# Cap_Array_100p_400n.net
KiCad netlist of a schematic drawn in Altium Designer
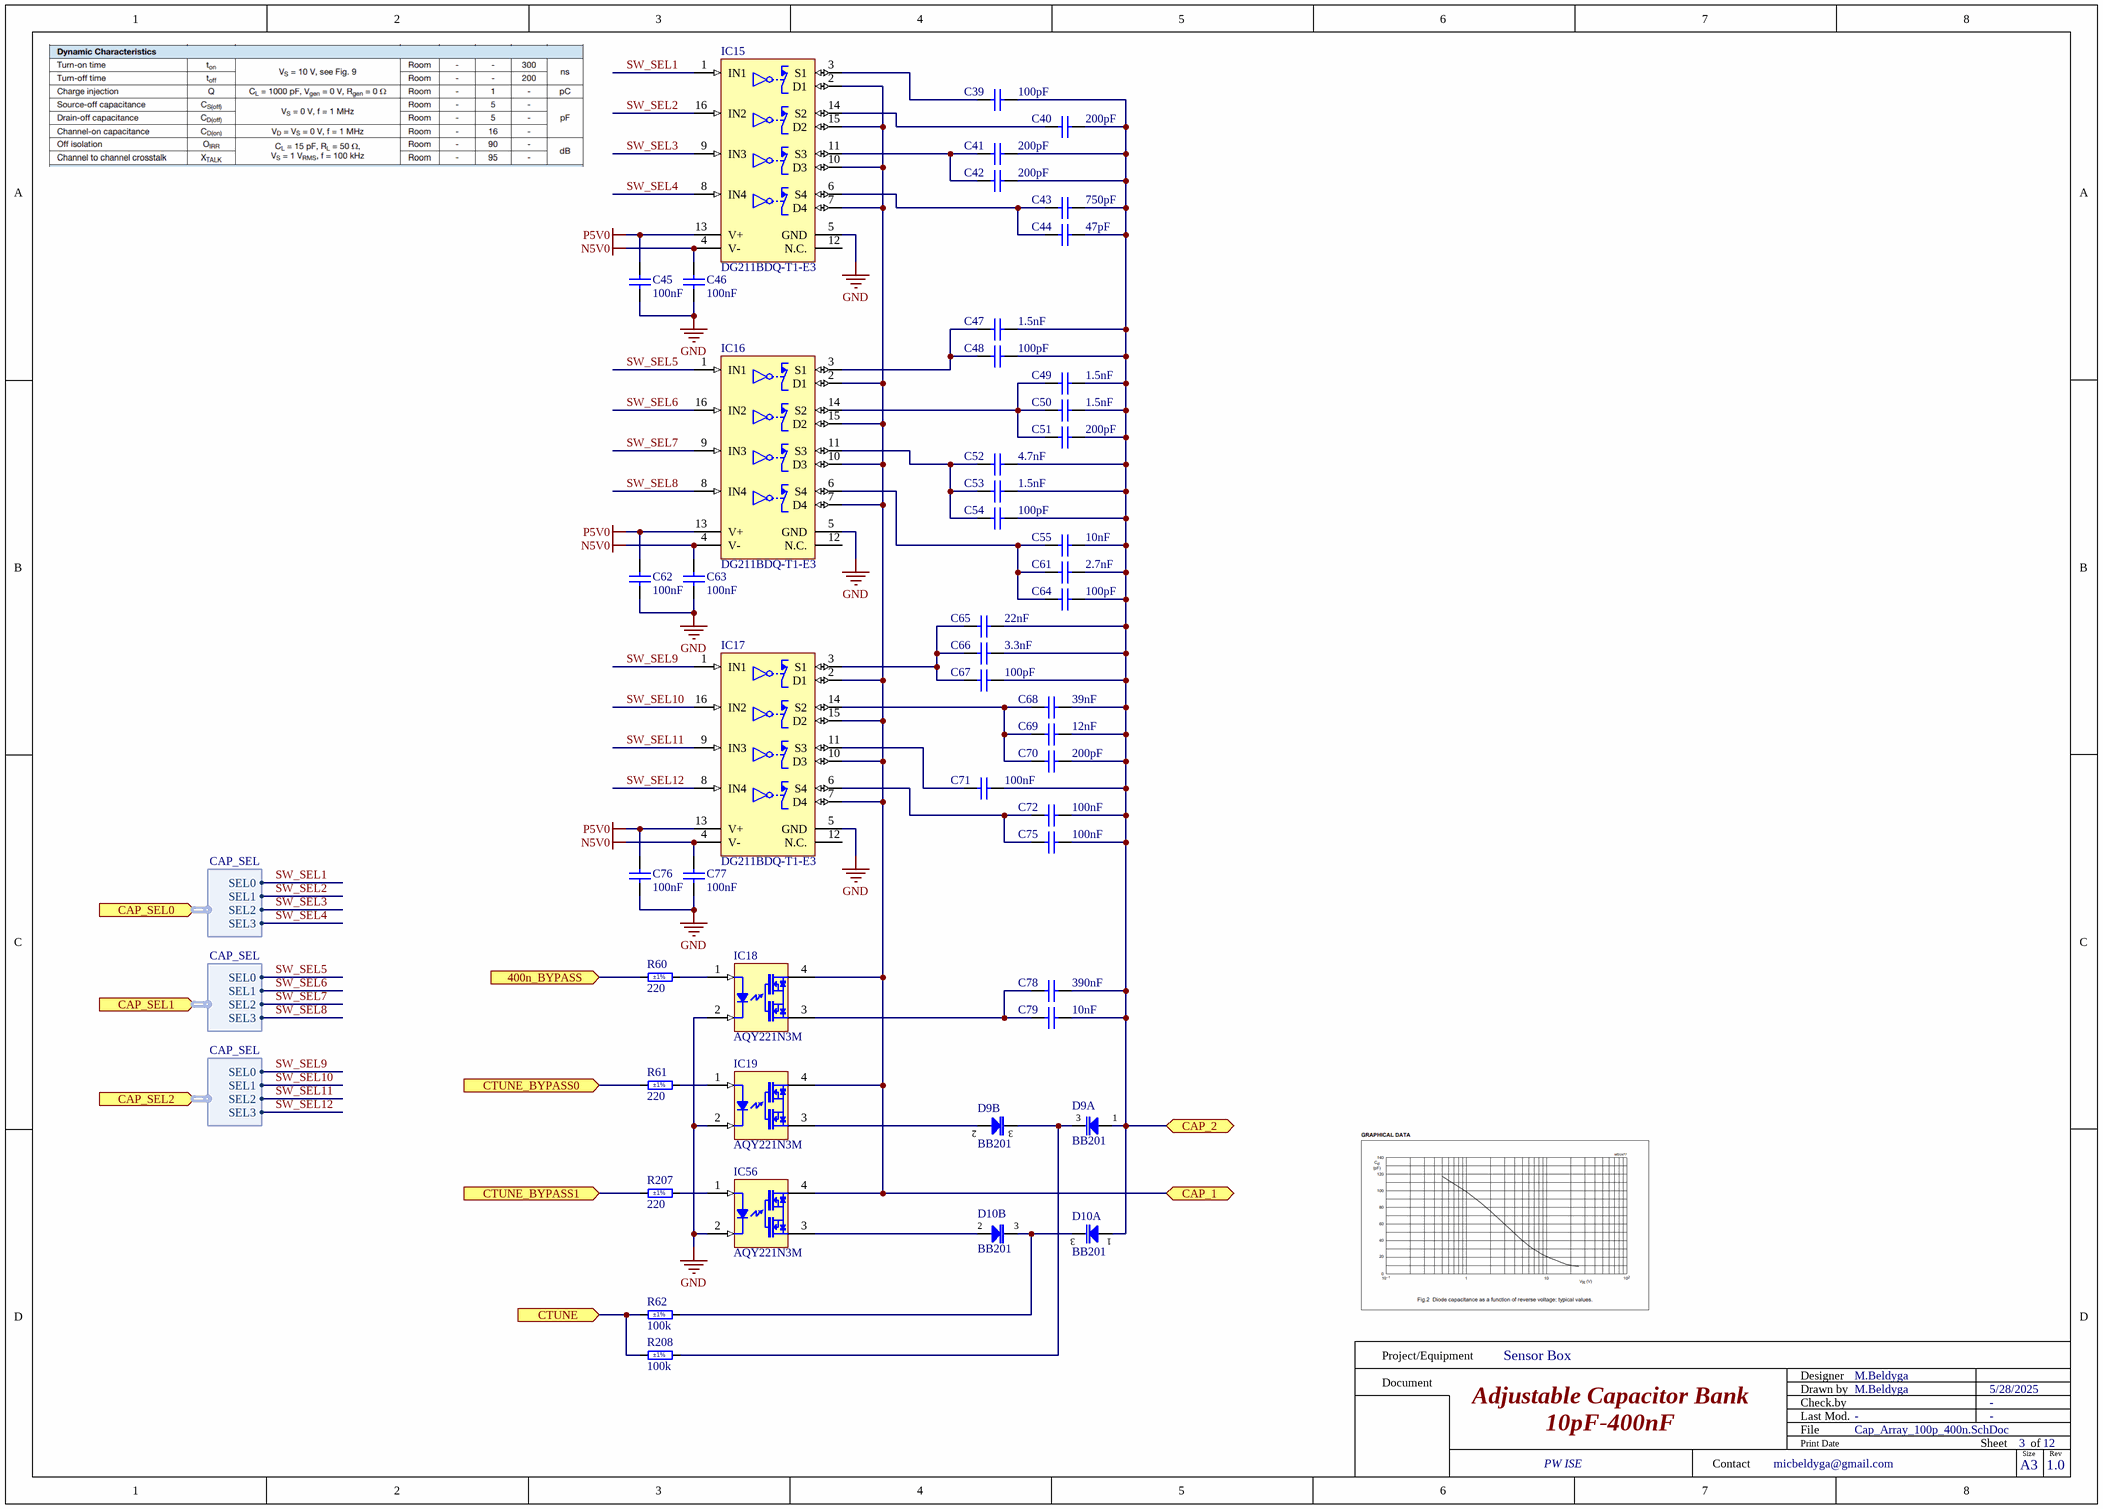
[diagram p0: Cap_Array_100p_400n.SchDoc]

(export (version "E")
  (design (tool "Eeschema 10.0.6"))
  (components
    (comp (ref "C39")
      (value "100pF")
      (footprint "CAPC1005X55N")
      (description "Non-polarised capacitor")
      (fields
        (field (name "PART NUMBER") "CC0402_100PF_25V_1%_C0G")
        (field (name "VOLTAGE") "25V")
        (field (name "AUTHOR") "CERN DEM HF")
      )
      (libsource (lib "Capacitors") (part "Capacitor - non polarized"))
    )
    (comp (ref "C40")
      (value "200pF")
      (footprint "CAPC1005X55N")
      (description "Multilayer Ceramic Capacitor, 200 pF, 50 V, ï¿½ 1%, C0G (NP0), 0402 [1005 Metric]")
      (fields
        (field (name "MANUFACTURER") "Murata")
        (field (name "MANUFACTURER PART NUMBER") "GCM1555C1H201FA16D")
      )
      (libsource (lib "mb") (part "0402 200pF 50V"))
    )
    (comp (ref "C41")
      (value "200pF")
      (footprint "CAPC1005X55N")
      (description "Multilayer Ceramic Capacitor, 200 pF, 50 V, ï¿½ 1%, C0G (NP0), 0402 [1005 Metric]")
      (fields
        (field (name "MANUFACTURER") "Murata")
        (field (name "MANUFACTURER PART NUMBER") "GCM1555C1H201FA16D")
      )
      (libsource (lib "mb") (part "0402 200pF 50V"))
    )
    (comp (ref "C42")
      (value "200pF")
      (footprint "CAPC1005X55N")
      (description "Multilayer Ceramic Capacitor, 200 pF, 50 V, ï¿½ 1%, C0G (NP0), 0402 [1005 Metric]")
      (fields
        (field (name "MANUFACTURER") "Murata")
        (field (name "MANUFACTURER PART NUMBER") "GCM1555C1H201FA16D")
      )
      (libsource (lib "mb") (part "0402 200pF 50V"))
    )
    (comp (ref "C43")
      (value "750pF")
      (footprint "CAPC1005X55N")
      (description "Cap Auto-grade 750PF 50VDC C0G 1% SMD 0402")
      (fields
        (field (name "MANUFACTURER") "Murata")
        (field (name "MANUFACTURER PART NUMBER") "GCM1555C1H751FA16D")
      )
      (libsource (lib "mb") (part "0402 750pF 50V"))
    )
    (comp (ref "C44")
      (value "47pF")
      (footprint "CAPC1005X55N")
      (description "Non-polarised capacitor")
      (fields
        (field (name "PART NUMBER") "CC0402_47PF_50V_1%_C0G_MURATA_GJM1555C1H470FB01D")
        (field (name "VOLTAGE") "50V")
        (field (name "AUTHOR") "CERN DEM BC")
      )
      (libsource (lib "Capacitors") (part "Capacitor - non polarized"))
    )
    (comp (ref "C45")
      (value "100nF")
      (footprint "CAPC1005X55N")
      (description "Non-polarised capacitor")
      (fields
        (field (name "PART NUMBER") "CC0402_100NF_50V_10%_X7R")
        (field (name "VOLTAGE") "50V")
        (field (name "AUTHOR") "CERN DEM MR")
      )
      (libsource (lib "Capacitors") (part "Capacitor - non polarized"))
    )
    (comp (ref "C46")
      (value "100nF")
      (footprint "CAPC1005X55N")
      (description "Non-polarised capacitor")
      (fields
        (field (name "PART NUMBER") "CC0402_100NF_50V_10%_X7R")
        (field (name "VOLTAGE") "50V")
        (field (name "AUTHOR") "CERN DEM MR")
      )
      (libsource (lib "Capacitors") (part "Capacitor - non polarized"))
    )
    (comp (ref "C47")
      (value "1.5nF")
      (footprint "CAPC1005X55N")
      (fields
        (field (name "MANUFACTURER") "KEMET")
        (field (name "MANUFACTURER PART NUMBER") "C0402C152F5GECAUTO")
      )
      (libsource (lib "mb") (part "0402 1.5nF 50V"))
    )
    (comp (ref "C48")
      (value "100pF")
      (footprint "CAPC1005X55N")
      (description "Non-polarised capacitor")
      (fields
        (field (name "PART NUMBER") "CC0402_100PF_25V_1%_C0G")
        (field (name "VOLTAGE") "25V")
        (field (name "AUTHOR") "CERN DEM HF")
      )
      (libsource (lib "Capacitors") (part "Capacitor - non polarized"))
    )
    (comp (ref "C49")
      (value "1.5nF")
      (footprint "CAPC1005X55N")
      (fields
        (field (name "MANUFACTURER") "KEMET")
        (field (name "MANUFACTURER PART NUMBER") "C0402C152F5GECAUTO")
      )
      (libsource (lib "mb") (part "0402 1.5nF 50V"))
    )
    (comp (ref "C50")
      (value "1.5nF")
      (footprint "CAPC1005X55N")
      (fields
        (field (name "MANUFACTURER") "KEMET")
        (field (name "MANUFACTURER PART NUMBER") "C0402C152F5GECAUTO")
      )
      (libsource (lib "mb") (part "0402 1.5nF 50V"))
    )
    (comp (ref "C51")
      (value "200pF")
      (footprint "CAPC1005X55N")
      (description "Multilayer Ceramic Capacitor, 200 pF, 50 V, ï¿½ 1%, C0G (NP0), 0402 [1005 Metric]")
      (fields
        (field (name "MANUFACTURER") "Murata")
        (field (name "MANUFACTURER PART NUMBER") "GCM1555C1H201FA16D")
      )
      (libsource (lib "mb") (part "0402 200pF 50V"))
    )
    (comp (ref "C52")
      (value "4.7nF")
      (footprint "CAPC1608X90N")
      (description "Cap Ceramic 0.0047uF 50V C0G 1% Pad SMD 0603 125°C Automotive T/R")
      (fields
        (field (name "MANUFACTURER") "Murata")
        (field (name "MANUFACTURER PART NUMBER") "GCM1885C1H472FA16D")
      )
      (libsource (lib "mb") (part "0603 4.7nF 50V"))
    )
    (comp (ref "C53")
      (value "1.5nF")
      (footprint "CAPC1005X55N")
      (fields
        (field (name "MANUFACTURER") "KEMET")
        (field (name "MANUFACTURER PART NUMBER") "C0402C152F5GECAUTO")
      )
      (libsource (lib "mb") (part "0402 1.5nF 50V"))
    )
    (comp (ref "C54")
      (value "100pF")
      (footprint "CAPC1005X55N")
      (description "Non-polarised capacitor")
      (fields
        (field (name "PART NUMBER") "CC0402_100PF_25V_1%_C0G")
        (field (name "VOLTAGE") "25V")
        (field (name "AUTHOR") "CERN DEM HF")
      )
      (libsource (lib "Capacitors") (part "Capacitor - non polarized"))
    )
    (comp (ref "C55")
      (value "10nF")
      (footprint "CAPC1608X90N")
      (description "Multilayer Ceramic Capacitors MLCC - SMD/SMT 25V 0.01uF C0G 0603 1% AEC-Q200")
      (fields
        (field (name "MANUFACTURER") "KEMET")
        (field (name "MANUFACTURER PART NUMBER") "C0603C103F3GECAUTO")
      )
      (libsource (lib "mb") (part "0603 10nF 25V"))
    )
    (comp (ref "C61")
      (value "2.7nF")
      (footprint "CAPC1608X90N")
      (description "Powerrain/Safety for Automotive AEC-Q200 Up to 125C Reflow soldering Flow soldering")
      (fields
        (field (name "MANUFACTURER") "Murata")
        (field (name "MANUFACTURER PART NUMBER") "GCM1885C1H272FA16J")
      )
      (libsource (lib "mb") (part "0603 2.7nF 50V"))
    )
    (comp (ref "C62")
      (value "100nF")
      (footprint "CAPC1005X55N")
      (description "Non-polarised capacitor")
      (fields
        (field (name "PART NUMBER") "CC0402_100NF_50V_10%_X7R")
        (field (name "VOLTAGE") "50V")
        (field (name "AUTHOR") "CERN DEM MR")
      )
      (libsource (lib "Capacitors") (part "Capacitor - non polarized"))
    )
    (comp (ref "C63")
      (value "100nF")
      (footprint "CAPC1005X55N")
      (description "Non-polarised capacitor")
      (fields
        (field (name "PART NUMBER") "CC0402_100NF_50V_10%_X7R")
        (field (name "VOLTAGE") "50V")
        (field (name "AUTHOR") "CERN DEM MR")
      )
      (libsource (lib "Capacitors") (part "Capacitor - non polarized"))
    )
    (comp (ref "C64")
      (value "100pF")
      (footprint "CAPC1005X55N")
      (description "Non-polarised capacitor")
      (fields
        (field (name "PART NUMBER") "CC0402_100PF_25V_1%_C0G")
        (field (name "VOLTAGE") "25V")
        (field (name "AUTHOR") "CERN DEM HF")
      )
      (libsource (lib "Capacitors") (part "Capacitor - non polarized"))
    )
    (comp (ref "C65")
      (value "22nF")
      (footprint "CAPC2012X95N")
      (description "0805 50V C0G 0.022uF 1% Automotive grade multilayer ceramic capacitor")
      (fields
        (field (name "MANUFACTURER") "Murata")
        (field (name "MANUFACTURER PART NUMBER") "GCM21B5C1H223FA16L")
      )
      (libsource (lib "mb") (part "0805 22nF 50V"))
    )
    (comp (ref "C66")
      (value "3.3nF")
      (footprint "CAPC1608X90N")
      (description "Cap Ceramic 0.0033uF 50V C0G 1% Pad SMD 0603 125°C Automotive T/R")
      (fields
        (field (name "MANUFACTURER") "Murata")
        (field (name "MANUFACTURER PART NUMBER") "GCM1885C1H332FA16D")
      )
      (libsource (lib "mb") (part "0603 3.3nF 50V"))
    )
    (comp (ref "C67")
      (value "100pF")
      (footprint "CAPC1005X55N")
      (description "Non-polarised capacitor")
      (fields
        (field (name "PART NUMBER") "CC0402_100PF_25V_1%_C0G")
        (field (name "VOLTAGE") "25V")
        (field (name "AUTHOR") "CERN DEM HF")
      )
      (libsource (lib "Capacitors") (part "Capacitor - non polarized"))
    )
    (comp (ref "C68")
      (value "39nF")
      (footprint "CAPC2012X95N")
      (description "Multilayer Ceramic Capacitors MLCC - SMD/SMT 0805 C0G 39000pF 2% 100VDC")
      (fields
        (field (name "MANUFACTURER") "Murata")
        (field (name "MANUFACTURER PART NUMBER") "GRM2195C2A393GE01J")
      )
      (libsource (lib "mb") (part "0805 39nF 100V"))
    )
    (comp (ref "C69")
      (value "12nF")
      (footprint "CAPC1608X90N")
      (description "Cap Ceramic 0.012uF 25V C0G 1% Pad SMD 0603 125°C Extreme Low ESR T/R")
      (fields
        (field (name "MANUFACTURER") "KEMET")
        (field (name "MANUFACTURER PART NUMBER") "C0603C123F3GACTU")
      )
      (libsource (lib "mb") (part "0603 12nF 25V"))
    )
    (comp (ref "C70")
      (value "200pF")
      (footprint "CAPC1005X55N")
      (description "Multilayer Ceramic Capacitor, 200 pF, 50 V, ï¿½ 1%, C0G (NP0), 0402 [1005 Metric]")
      (fields
        (field (name "MANUFACTURER") "Murata")
        (field (name "MANUFACTURER PART NUMBER") "GCM1555C1H201FA16D")
      )
      (libsource (lib "mb") (part "0402 200pF 50V"))
    )
    (comp (ref "C71")
      (value "100nF")
      (footprint "CAPC1810X06N")
      (description "Cap Cer 0.1UF 50V C0G/NP0 0704")
      (fields
        (field (name "MANUFACTURER") "Murata")
        (field (name "MANUFACTURER PART NUMBER") "GRMJN65C1H104GE01J")
      )
      (libsource (lib "mb") (part "0704 100nF 50V"))
    )
    (comp (ref "C72")
      (value "100nF")
      (footprint "CAPC1810X06N")
      (description "Cap Cer 0.1UF 50V C0G/NP0 0704")
      (fields
        (field (name "MANUFACTURER") "Murata")
        (field (name "MANUFACTURER PART NUMBER") "GRMJN65C1H104GE01J")
      )
      (libsource (lib "mb") (part "0704 100nF 50V"))
    )
    (comp (ref "C75")
      (value "100nF")
      (footprint "CAPC1810X06N")
      (description "Cap Cer 0.1UF 50V C0G/NP0 0704")
      (fields
        (field (name "MANUFACTURER") "Murata")
        (field (name "MANUFACTURER PART NUMBER") "GRMJN65C1H104GE01J")
      )
      (libsource (lib "mb") (part "0704 100nF 50V"))
    )
    (comp (ref "C76")
      (value "100nF")
      (footprint "CAPC1005X55N")
      (description "Non-polarised capacitor")
      (fields
        (field (name "PART NUMBER") "CC0402_100NF_50V_10%_X7R")
        (field (name "VOLTAGE") "50V")
        (field (name "AUTHOR") "CERN DEM MR")
      )
      (libsource (lib "Capacitors") (part "Capacitor - non polarized"))
    )
    (comp (ref "C77")
      (value "100nF")
      (footprint "CAPC1005X55N")
      (description "Non-polarised capacitor")
      (fields
        (field (name "PART NUMBER") "CC0402_100NF_50V_10%_X7R")
        (field (name "VOLTAGE") "50V")
        (field (name "AUTHOR") "CERN DEM MR")
      )
      (libsource (lib "Capacitors") (part "Capacitor - non polarized"))
    )
    (comp (ref "C78")
      (value "390nF")
      (footprint "CAPC1608X90N")
      (description "Cap Ceramic 0.39uF 16V X7R 5% Pad SMD 0603 125C T/R")
      (fields
        (field (name "MANUFACTURER") "KEMET")
        (field (name "MANUFACTURER PART NUMBER") "C0603C394J4RACTU")
      )
      (libsource (lib "mb") (part "0603 390nF 16V"))
    )
    (comp (ref "C79")
      (value "10nF")
      (footprint "CAPC1608X90N")
      (description "Multilayer Ceramic Capacitors MLCC - SMD/SMT 25V 0.01uF C0G 0603 1% AEC-Q200")
      (fields
        (field (name "MANUFACTURER") "KEMET")
        (field (name "MANUFACTURER PART NUMBER") "C0603C103F3GECAUTO")
      )
      (libsource (lib "mb") (part "0603 10nF 25V"))
    )
    (comp (ref "D9")
      (value "BB201")
      (footprint "SOT95P230X110-3N")
      (description "Dual Common Cathode Varicap Diodes")
      (fields
        (field (name "VOLTAGE") "15V")
        (field (name "POWER") "20mA")
        (field (name "AUTHOR") "CERN DEM JLC")
      )
      (libsource (lib "ICs And Semiconductors") (part "Diode Varicap x2 A1C3_A2C3"))
    )
    (comp (ref "D10")
      (value "BB201")
      (footprint "SOT95P230X110-3N")
      (description "Dual Common Cathode Varicap Diodes")
      (fields
        (field (name "VOLTAGE") "15V")
        (field (name "POWER") "20mA")
        (field (name "AUTHOR") "CERN DEM JLC")
      )
      (libsource (lib "") (part "Diode Varicap x2 A1C3_A2C3_1"))
    )
    (comp (ref "IC15")
      (value "DG211BDQ-T1-E3")
      (footprint "SOP65P640X120-16N")
      (description "DG211B Series SPST 22 V 50 Ohm Surface Mount Improved Analog Switch - TSSOP-16")
      (fields (field (name "MANUFACTURER") "Vishay Siliconix"))
      (libsource (lib "mb") (part "DG211BDQ-T1-E3"))
    )
    (comp (ref "IC16")
      (value "DG211BDQ-T1-E3")
      (footprint "SOP65P640X120-16N")
      (description "DG211B Series SPST 22 V 50 Ohm Surface Mount Improved Analog Switch - TSSOP-16")
      (fields (field (name "MANUFACTURER") "Vishay Siliconix"))
      (libsource (lib "mb") (part "DG211BDQ-T1-E3"))
    )
    (comp (ref "IC17")
      (value "DG211BDQ-T1-E3")
      (footprint "SOP65P640X120-16N")
      (description "DG211B Series SPST 22 V 50 Ohm Surface Mount Improved Analog Switch - TSSOP-16")
      (fields (field (name "MANUFACTURER") "Vishay Siliconix"))
      (libsource (lib "mb") (part "DG211BDQ-T1-E3"))
    )
    (comp (ref "IC18")
      (value "AQY221N3M")
      (footprint "PANASONIC_AQY22(SON)")
      (description "PhotoMOS Relay")
      (fields (field (name "MANUFACTURER") "PANASONIC") (field (name "AUTHOR") "CERN DEM JLC"))
      (libsource (lib "ICs And Semiconductors") (part "PhotoMOS Relay x1 Type5_a"))
    )
    (comp (ref "IC19")
      (value "AQY221N3M")
      (footprint "PANASONIC_AQY22(SON)")
      (description "PhotoMOS Relay")
      (fields (field (name "MANUFACTURER") "PANASONIC") (field (name "AUTHOR") "CERN DEM JLC"))
      (libsource (lib "ICs And Semiconductors") (part "PhotoMOS Relay x1 Type5_a"))
    )
    (comp (ref "IC56")
      (value "AQY221N3M")
      (footprint "PANASONIC_AQY22(SON)")
      (description "PhotoMOS Relay")
      (fields (field (name "MANUFACTURER") "PANASONIC") (field (name "AUTHOR") "CERN DEM JLC"))
      (libsource (lib "ICs And Semiconductors") (part "PhotoMOS Relay x1 Type5_a"))
    )
    (comp (ref "R60")
      (value "220")
      (footprint "RESC1005X40N")
      (description "Resistor - 1%")
      (fields
        (field (name "TOLERANCE") "±1%")
        (field (name "PART NUMBER") "R0402_220R_1%_0.0625W_100PPM")
        (field (name "POWER") "0.0625W")
        (field (name "AUTHOR") "CERN DEM JLC")
      )
      (libsource (lib "Resistors") (part "Resistor - 1%"))
    )
    (comp (ref "R61")
      (value "220")
      (footprint "RESC1005X40N")
      (description "Resistor - 1%")
      (fields
        (field (name "TOLERANCE") "±1%")
        (field (name "PART NUMBER") "R0402_220R_1%_0.0625W_100PPM")
        (field (name "POWER") "0.0625W")
        (field (name "AUTHOR") "CERN DEM JLC")
      )
      (libsource (lib "Resistors") (part "Resistor - 1%"))
    )
    (comp (ref "R62")
      (value "100k")
      (footprint "RESC1005X40N")
      (description "Resistor - 1%")
      (fields
        (field (name "TOLERANCE") "±1%")
        (field (name "PART NUMBER") "R0402_100K_1%_0.0625W_100PPM")
        (field (name "POWER") "0.0625W")
        (field (name "AUTHOR") "CERN DEM JLC")
      )
      (libsource (lib "Resistors") (part "Resistor - 1%"))
    )
    (comp (ref "R207")
      (value "220")
      (footprint "RESC1005X40N")
      (description "Resistor - 1%")
      (fields
        (field (name "TOLERANCE") "±1%")
        (field (name "PART NUMBER") "R0402_220R_1%_0.0625W_100PPM")
        (field (name "POWER") "0.0625W")
        (field (name "AUTHOR") "CERN DEM JLC")
      )
      (libsource (lib "Resistors") (part "Resistor - 1%"))
    )
    (comp (ref "R208")
      (value "100k")
      (footprint "RESC1005X40N")
      (description "Resistor - 1%")
      (fields
        (field (name "TOLERANCE") "±1%")
        (field (name "PART NUMBER") "R0402_100K_1%_0.0625W_100PPM")
        (field (name "POWER") "0.0625W")
        (field (name "AUTHOR") "CERN DEM JLC")
      )
      (libsource (lib "Resistors") (part "Resistor - 1%"))
    )
  )
  (nets
    (net (code "2") (name "/400n_BYPASS") (class "Default")
      (node (ref "R60") (pin "1") (pinfunction "1_1") (pintype "passive"))
    )
    (net (code "3") (name "/CAP_1") (class "Default")
      (node (ref "IC15") (pin "10") (pinfunction "D3_10") (pintype "bidirectional"))
      (node (ref "IC15") (pin "15") (pinfunction "D2_15") (pintype "bidirectional"))
      (node (ref "IC15") (pin "2") (pinfunction "D1_2") (pintype "bidirectional"))
      (node (ref "IC15") (pin "7") (pinfunction "D4_7") (pintype "bidirectional"))
      (node (ref "IC16") (pin "10") (pinfunction "D3_10") (pintype "bidirectional"))
      (node (ref "IC16") (pin "15") (pinfunction "D2_15") (pintype "bidirectional"))
      (node (ref "IC16") (pin "2") (pinfunction "D1_2") (pintype "bidirectional"))
      (node (ref "IC16") (pin "7") (pinfunction "D4_7") (pintype "bidirectional"))
      (node (ref "IC17") (pin "10") (pinfunction "D3_10") (pintype "bidirectional"))
      (node (ref "IC17") (pin "15") (pinfunction "D2_15") (pintype "bidirectional"))
      (node (ref "IC17") (pin "2") (pinfunction "D1_2") (pintype "bidirectional"))
      (node (ref "IC17") (pin "7") (pinfunction "D4_7") (pintype "bidirectional"))
      (node (ref "IC18") (pin "4") (pinfunction "E_4") (pintype "open_emitter"))
      (node (ref "IC19") (pin "4") (pinfunction "E_4") (pintype "open_emitter"))
      (node (ref "IC56") (pin "4") (pinfunction "E_4") (pintype "open_emitter"))
    )
    (net (code "4") (name "/CAP_2") (class "Default")
      (node (ref "C39") (pin "2") (pinfunction "2_2") (pintype "passive"))
      (node (ref "C40") (pin "1") (pinfunction "1_1") (pintype "passive"))
      (node (ref "C41") (pin "1") (pinfunction "1_1") (pintype "passive"))
      (node (ref "C42") (pin "1") (pinfunction "1_1") (pintype "passive"))
      (node (ref "C43") (pin "1") (pinfunction "1_1") (pintype "passive"))
      (node (ref "C44") (pin "2") (pinfunction "2_2") (pintype "passive"))
      (node (ref "C47") (pin "1") (pinfunction "1_1") (pintype "passive"))
      (node (ref "C48") (pin "2") (pinfunction "2_2") (pintype "passive"))
      (node (ref "C49") (pin "1") (pinfunction "1_1") (pintype "passive"))
      (node (ref "C50") (pin "1") (pinfunction "1_1") (pintype "passive"))
      (node (ref "C51") (pin "1") (pinfunction "1_1") (pintype "passive"))
      (node (ref "C52") (pin "1") (pinfunction "1_1") (pintype "passive"))
      (node (ref "C53") (pin "1") (pinfunction "1_1") (pintype "passive"))
      (node (ref "C54") (pin "2") (pinfunction "2_2") (pintype "passive"))
      (node (ref "C55") (pin "1") (pinfunction "1_1") (pintype "passive"))
      (node (ref "C61") (pin "1") (pinfunction "1_1") (pintype "passive"))
      (node (ref "C64") (pin "2") (pinfunction "2_2") (pintype "passive"))
      (node (ref "C65") (pin "1") (pinfunction "1_1") (pintype "passive"))
      (node (ref "C66") (pin "1") (pinfunction "1_1") (pintype "passive"))
      (node (ref "C67") (pin "2") (pinfunction "2_2") (pintype "passive"))
      (node (ref "C68") (pin "1") (pinfunction "1_1") (pintype "passive"))
      (node (ref "C69") (pin "1") (pinfunction "1_1") (pintype "passive"))
      (node (ref "C70") (pin "1") (pinfunction "1_1") (pintype "passive"))
      (node (ref "C71") (pin "1") (pinfunction "1_1") (pintype "passive"))
      (node (ref "C72") (pin "1") (pinfunction "1_1") (pintype "passive"))
      (node (ref "C75") (pin "1") (pinfunction "1_1") (pintype "passive"))
      (node (ref "C78") (pin "1") (pinfunction "1_1") (pintype "passive"))
      (node (ref "C79") (pin "1") (pinfunction "1_1") (pintype "passive"))
      (node (ref "D10") (pin "1") (pinfunction "A_1") (pintype "passive"))
      (node (ref "D9") (pin "1") (pinfunction "A_1") (pintype "passive"))
    )
    (net (code "5") (name "/CTUNE") (class "Default")
      (node (ref "R208") (pin "2") (pinfunction "2_2") (pintype "passive"))
      (node (ref "R62") (pin "2") (pinfunction "2_2") (pintype "passive"))
    )
    (net (code "6") (name "/CTUNE_BYPASS0") (class "Default")
      (node (ref "R61") (pin "1") (pinfunction "1_1") (pintype "passive"))
    )
    (net (code "7") (name "/CTUNE_BYPASS1") (class "Default")
      (node (ref "R207") (pin "1") (pinfunction "1_1") (pintype "passive"))
    )
    (net (code "8") (name "/SW_SEL1") (class "Default")
      (node (ref "IC15") (pin "1") (pinfunction "IN1_1") (pintype "input"))
    )
    (net (code "9") (name "/SW_SEL2") (class "Default")
      (node (ref "IC15") (pin "16") (pinfunction "IN2_16") (pintype "input"))
    )
    (net (code "10") (name "/SW_SEL3") (class "Default")
      (node (ref "IC15") (pin "9") (pinfunction "IN3_9") (pintype "input"))
    )
    (net (code "11") (name "/SW_SEL4") (class "Default")
      (node (ref "IC15") (pin "8") (pinfunction "IN4_8") (pintype "input"))
    )
    (net (code "12") (name "/SW_SEL5") (class "Default")
      (node (ref "IC16") (pin "1") (pinfunction "IN1_1") (pintype "input"))
    )
    (net (code "13") (name "/SW_SEL6") (class "Default")
      (node (ref "IC16") (pin "16") (pinfunction "IN2_16") (pintype "input"))
    )
    (net (code "14") (name "/SW_SEL7") (class "Default")
      (node (ref "IC16") (pin "9") (pinfunction "IN3_9") (pintype "input"))
    )
    (net (code "15") (name "/SW_SEL8") (class "Default")
      (node (ref "IC16") (pin "8") (pinfunction "IN4_8") (pintype "input"))
    )
    (net (code "16") (name "/SW_SEL9") (class "Default")
      (node (ref "IC17") (pin "1") (pinfunction "IN1_1") (pintype "input"))
    )
    (net (code "17") (name "/SW_SEL10") (class "Default")
      (node (ref "IC17") (pin "16") (pinfunction "IN2_16") (pintype "input"))
    )
    (net (code "18") (name "/SW_SEL11") (class "Default")
      (node (ref "IC17") (pin "9") (pinfunction "IN3_9") (pintype "input"))
    )
    (net (code "19") (name "/SW_SEL12") (class "Default")
      (node (ref "IC17") (pin "8") (pinfunction "IN4_8") (pintype "input"))
    )
    (net (code "21") (name "GND") (class "Default")
      (node (ref "C45") (pin "1") (pinfunction "1_1") (pintype "passive"))
      (node (ref "C46") (pin "1") (pinfunction "1_1") (pintype "passive"))
      (node (ref "C62") (pin "1") (pinfunction "1_1") (pintype "passive"))
      (node (ref "C63") (pin "1") (pinfunction "1_1") (pintype "passive"))
      (node (ref "C76") (pin "1") (pinfunction "1_1") (pintype "passive"))
      (node (ref "C77") (pin "1") (pinfunction "1_1") (pintype "passive"))
      (node (ref "IC15") (pin "5") (pinfunction "GND_5") (pintype "power_in"))
      (node (ref "IC16") (pin "5") (pinfunction "GND_5") (pintype "power_in"))
      (node (ref "IC17") (pin "5") (pinfunction "GND_5") (pintype "power_in"))
      (node (ref "IC18") (pin "2") (pinfunction "K_2") (pintype "input"))
      (node (ref "IC19") (pin "2") (pinfunction "K_2") (pintype "input"))
      (node (ref "IC56") (pin "2") (pinfunction "K_2") (pintype "input"))
    )
    (net (code "22") (name "N5V0") (class "Default")
      (node (ref "C46") (pin "2") (pinfunction "2_2") (pintype "passive"))
      (node (ref "C63") (pin "2") (pinfunction "2_2") (pintype "passive"))
      (node (ref "C77") (pin "2") (pinfunction "2_2") (pintype "passive"))
      (node (ref "IC15") (pin "4") (pinfunction "V-_4") (pintype "power_in"))
      (node (ref "IC16") (pin "4") (pinfunction "V-_4") (pintype "power_in"))
      (node (ref "IC17") (pin "4") (pinfunction "V-_4") (pintype "power_in"))
    )
    (net (code "23") (name "Net-(D9A-COMC)") (class "Default")
      (node (ref "D9") (pin "3") (pinfunction "COMC_3") (pintype "passive"))
      (node (ref "R208") (pin "1") (pinfunction "1_1") (pintype "passive"))
    )
    (net (code "24") (name "Net-(D9B-A)") (class "Default")
      (node (ref "D9") (pin "2") (pinfunction "A_2") (pintype "passive"))
      (node (ref "IC19") (pin "3") (pinfunction "C_3") (pintype "open_collector"))
    )
    (net (code "25") (name "Net-(D10A-COMC)") (class "Default")
      (node (ref "D10") (pin "3") (pinfunction "COMC_3") (pintype "passive"))
      (node (ref "R62") (pin "1") (pinfunction "1_1") (pintype "passive"))
    )
    (net (code "26") (name "Net-(D10B-A)") (class "Default")
      (node (ref "D10") (pin "2") (pinfunction "A_2") (pintype "passive"))
      (node (ref "IC56") (pin "3") (pinfunction "C_3") (pintype "open_collector"))
    )
    (net (code "27") (name "Net-(IC15-S1)") (class "Default")
      (node (ref "C39") (pin "1") (pinfunction "1_1") (pintype "passive"))
      (node (ref "IC15") (pin "3") (pinfunction "S1_3") (pintype "bidirectional"))
    )
    (net (code "28") (name "Net-(IC15-S2)") (class "Default")
      (node (ref "C40") (pin "2") (pinfunction "2_2") (pintype "passive"))
      (node (ref "IC15") (pin "14") (pinfunction "S2_14") (pintype "bidirectional"))
    )
    (net (code "29") (name "Net-(IC15-S3)") (class "Default")
      (node (ref "C41") (pin "2") (pinfunction "2_2") (pintype "passive"))
      (node (ref "C42") (pin "2") (pinfunction "2_2") (pintype "passive"))
      (node (ref "IC15") (pin "11") (pinfunction "S3_11") (pintype "bidirectional"))
    )
    (net (code "30") (name "Net-(IC15-S4)") (class "Default")
      (node (ref "C43") (pin "2") (pinfunction "2_2") (pintype "passive"))
      (node (ref "C44") (pin "1") (pinfunction "1_1") (pintype "passive"))
      (node (ref "IC15") (pin "6") (pinfunction "S4_6") (pintype "bidirectional"))
    )
    (net (code "31") (name "Net-(IC16-S1)") (class "Default")
      (node (ref "C47") (pin "2") (pinfunction "2_2") (pintype "passive"))
      (node (ref "C48") (pin "1") (pinfunction "1_1") (pintype "passive"))
      (node (ref "IC16") (pin "3") (pinfunction "S1_3") (pintype "bidirectional"))
    )
    (net (code "32") (name "Net-(IC16-S2)") (class "Default")
      (node (ref "C49") (pin "2") (pinfunction "2_2") (pintype "passive"))
      (node (ref "C50") (pin "2") (pinfunction "2_2") (pintype "passive"))
      (node (ref "C51") (pin "2") (pinfunction "2_2") (pintype "passive"))
      (node (ref "IC16") (pin "14") (pinfunction "S2_14") (pintype "bidirectional"))
    )
    (net (code "33") (name "Net-(IC16-S3)") (class "Default")
      (node (ref "C52") (pin "2") (pinfunction "2_2") (pintype "passive"))
      (node (ref "C53") (pin "2") (pinfunction "2_2") (pintype "passive"))
      (node (ref "C54") (pin "1") (pinfunction "1_1") (pintype "passive"))
      (node (ref "IC16") (pin "11") (pinfunction "S3_11") (pintype "bidirectional"))
    )
    (net (code "34") (name "Net-(IC16-S4)") (class "Default")
      (node (ref "C55") (pin "2") (pinfunction "2_2") (pintype "passive"))
      (node (ref "C61") (pin "2") (pinfunction "2_2") (pintype "passive"))
      (node (ref "C64") (pin "1") (pinfunction "1_1") (pintype "passive"))
      (node (ref "IC16") (pin "6") (pinfunction "S4_6") (pintype "bidirectional"))
    )
    (net (code "35") (name "Net-(IC17-S1)") (class "Default")
      (node (ref "C65") (pin "2") (pinfunction "2_2") (pintype "passive"))
      (node (ref "C66") (pin "2") (pinfunction "2_2") (pintype "passive"))
      (node (ref "C67") (pin "1") (pinfunction "1_1") (pintype "passive"))
      (node (ref "IC17") (pin "3") (pinfunction "S1_3") (pintype "bidirectional"))
    )
    (net (code "36") (name "Net-(IC17-S2)") (class "Default")
      (node (ref "C68") (pin "2") (pinfunction "2_2") (pintype "passive"))
      (node (ref "C69") (pin "2") (pinfunction "2_2") (pintype "passive"))
      (node (ref "C70") (pin "2") (pinfunction "2_2") (pintype "passive"))
      (node (ref "IC17") (pin "14") (pinfunction "S2_14") (pintype "bidirectional"))
    )
    (net (code "37") (name "Net-(IC17-S3)") (class "Default")
      (node (ref "C71") (pin "2") (pinfunction "2_2") (pintype "passive"))
      (node (ref "IC17") (pin "11") (pinfunction "S3_11") (pintype "bidirectional"))
    )
    (net (code "38") (name "Net-(IC17-S4)") (class "Default")
      (node (ref "C72") (pin "2") (pinfunction "2_2") (pintype "passive"))
      (node (ref "C75") (pin "2") (pinfunction "2_2") (pintype "passive"))
      (node (ref "IC17") (pin "6") (pinfunction "S4_6") (pintype "bidirectional"))
    )
    (net (code "39") (name "Net-(IC18-A)") (class "Default")
      (node (ref "IC18") (pin "1") (pinfunction "A_1") (pintype "input"))
      (node (ref "R60") (pin "2") (pinfunction "2_2") (pintype "passive"))
    )
    (net (code "40") (name "Net-(IC18-C)") (class "Default")
      (node (ref "C78") (pin "2") (pinfunction "2_2") (pintype "passive"))
      (node (ref "C79") (pin "2") (pinfunction "2_2") (pintype "passive"))
      (node (ref "IC18") (pin "3") (pinfunction "C_3") (pintype "open_collector"))
    )
    (net (code "41") (name "Net-(IC19-A)") (class "Default")
      (node (ref "IC19") (pin "1") (pinfunction "A_1") (pintype "input"))
      (node (ref "R61") (pin "2") (pinfunction "2_2") (pintype "passive"))
    )
    (net (code "42") (name "Net-(IC56-A)") (class "Default")
      (node (ref "IC56") (pin "1") (pinfunction "A_1") (pintype "input"))
      (node (ref "R207") (pin "2") (pinfunction "2_2") (pintype "passive"))
    )
    (net (code "43") (name "P5V0") (class "Default")
      (node (ref "C45") (pin "2") (pinfunction "2_2") (pintype "passive"))
      (node (ref "C62") (pin "2") (pinfunction "2_2") (pintype "passive"))
      (node (ref "C76") (pin "2") (pinfunction "2_2") (pintype "passive"))
      (node (ref "IC15") (pin "13") (pinfunction "V+_13") (pintype "power_in"))
      (node (ref "IC16") (pin "13") (pinfunction "V+_13") (pintype "power_in"))
      (node (ref "IC17") (pin "13") (pinfunction "V+_13") (pintype "power_in"))
    )
    (net (code "44") (name "unconnected-(IC15-N.C.-Pad12)") (class "Default")
      (node (ref "IC15") (pin "12") (pinfunction "N.C._12") (pintype "power_in"))
    )
    (net (code "45") (name "unconnected-(IC16-N.C.-Pad12)") (class "Default")
      (node (ref "IC16") (pin "12") (pinfunction "N.C._12") (pintype "power_in"))
    )
    (net (code "46") (name "unconnected-(IC17-N.C.-Pad12)") (class "Default")
      (node (ref "IC17") (pin "12") (pinfunction "N.C._12") (pintype "power_in"))
    )
  )
)
